# Lipo.net
KiCad netlist of a schematic drawn in EAGLE
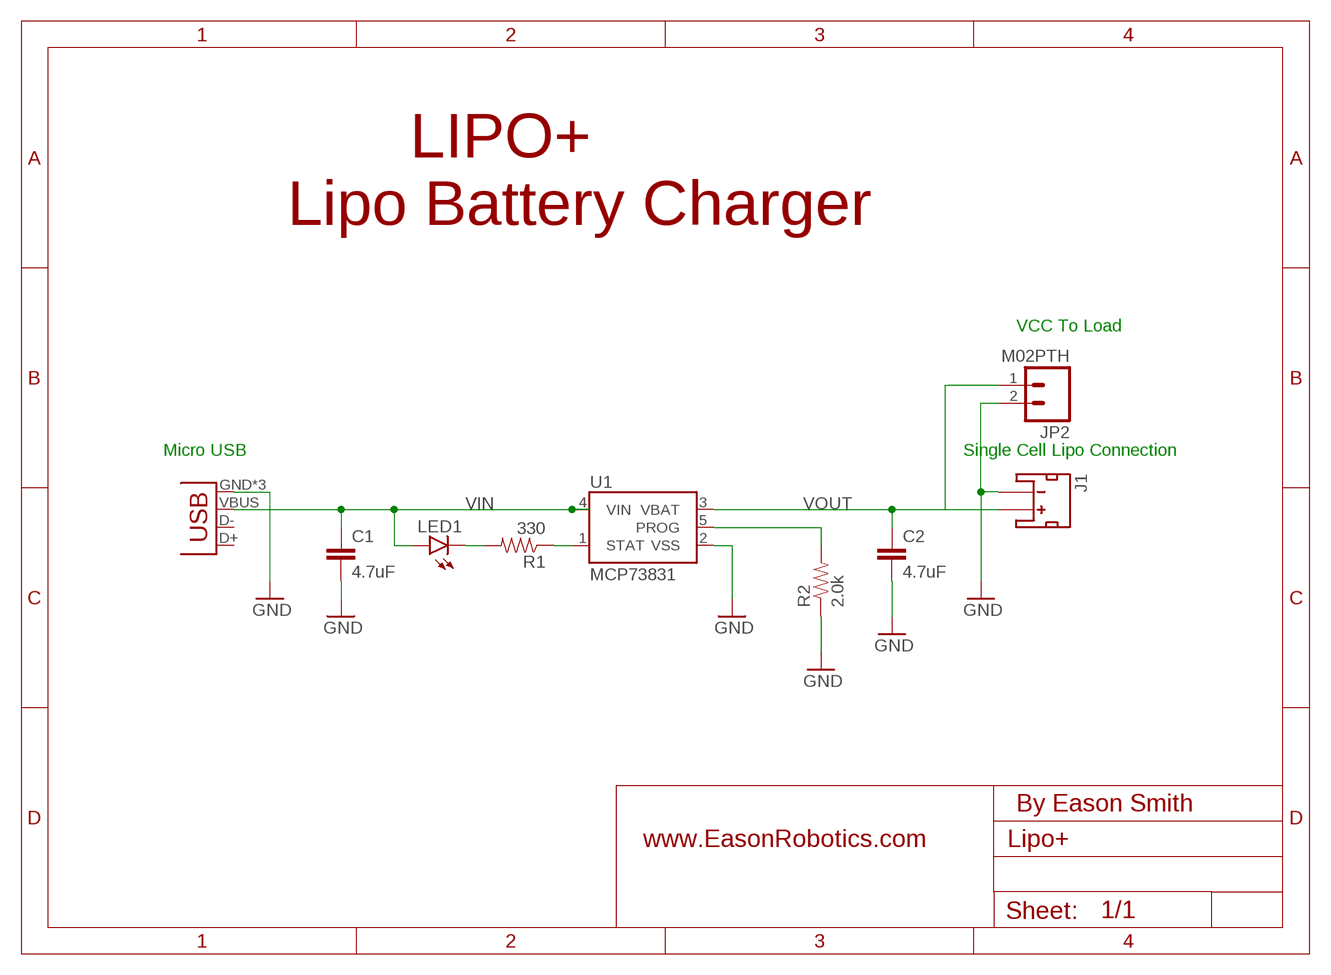
[diagram p0: schematic, sheet 1]

(export (version "E")
  (design (tool "Eeschema 10.0.6"))
  (components
    (comp (ref "C1")
      (value "4.7uF")
      (footprint "eagle-import:0603-CAP")
      (libsource (lib "eagle-import") (part "4.7UF-6.3V-10%(0603)0603"))
    )
    (comp (ref "C2")
      (value "4.7uF")
      (footprint "eagle-import:0603-CAP")
      (libsource (lib "eagle-import") (part "4.7UF-6.3V-10%(0603)0603"))
    )
    (comp (ref "J1")
      (value "JST_2MM_MALE")
      (footprint "eagle-import:JST-2-SMD")
      (libsource (lib "eagle-import") (part "JST_2MM_MALE"))
    )
    (comp (ref "JP1")
      (value "USB-MICROB")
      (footprint "eagle-import:USB-MICROB")
      (libsource (lib "eagle-import") (part "USB-MICROB"))
    )
    (comp (ref "JP2")
      (value "M02PTH")
      (footprint "eagle-import:1X02")
      (libsource (lib "eagle-import") (part "M02PTH"))
    )
    (comp (ref "LED1")
      (value "LED0603")
      (footprint "eagle-import:LED-0603")
      (libsource (lib "eagle-import") (part "LED0603"))
    )
    (comp (ref "R1")
      (value "330")
      (footprint "eagle-import:0603-RES")
      (libsource (lib "eagle-import") (part "330OHM1/10W1%(0603)"))
    )
    (comp (ref "R2")
      (value "2.0k")
      (footprint "eagle-import:0603-RES")
      (libsource (lib "eagle-import") (part "2.0KOHM1/10W5%(0603)"))
    )
    (comp (ref "U1")
      (value "MCP73831")
      (footprint "eagle-import:SOT23-5")
      (libsource (lib "eagle-import") (part "MCP73831"))
    )
  )
  (nets
    (net (code "1") (name "/VIN") (class "Default")
      (node (ref "C1") (pin "1") (pinfunction "1_1") (pintype "passive"))
      (node (ref "JP1") (pin "VBUS") (pinfunction "VBUS_VBUS") (pintype "bidirectional"))
      (node (ref "LED1") (pin "A") (pinfunction "A_A") (pintype "passive"))
      (node (ref "U1") (pin "4") (pinfunction "VIN_4") (pintype "power_in"))
    )
    (net (code "2") (name "/VOUT") (class "Default")
      (node (ref "C2") (pin "1") (pinfunction "1_1") (pintype "passive"))
      (node (ref "J1") (pin "2") (pinfunction "+_2") (pintype "bidirectional"))
      (node (ref "JP2") (pin "1") (pinfunction "1_1") (pintype "passive"))
      (node (ref "U1") (pin "3") (pinfunction "VBAT_3") (pintype "power_in"))
    )
    (net (code "3") (name "GND") (class "Default")
      (node (ref "C1") (pin "2") (pinfunction "2_2") (pintype "passive"))
      (node (ref "C2") (pin "2") (pinfunction "2_2") (pintype "passive"))
      (node (ref "J1") (pin "1") (pinfunction "-_1") (pintype "bidirectional"))
      (node (ref "JP1") (pin "GND") (pinfunction "GND_GND") (pintype "bidirectional"))
      (node (ref "JP1") (pin "MT1") (pinfunction "GND_MT1") (pintype "bidirectional"))
      (node (ref "JP1") (pin "MT2") (pinfunction "GND_MT2") (pintype "bidirectional"))
      (node (ref "JP2") (pin "2") (pinfunction "2_2") (pintype "passive"))
      (node (ref "R2") (pin "1") (pinfunction "1_1") (pintype "passive"))
      (node (ref "U1") (pin "2") (pinfunction "VSS_2") (pintype "power_in"))
    )
    (net (code "4") (name "Net-(LED1-PadC)") (class "Default")
      (node (ref "LED1") (pin "C") (pinfunction "C_C") (pintype "passive"))
      (node (ref "R1") (pin "2") (pinfunction "2_2") (pintype "passive"))
    )
    (net (code "5") (name "Net-(U1-PROG)") (class "Default")
      (node (ref "R2") (pin "2") (pinfunction "2_2") (pintype "passive"))
      (node (ref "U1") (pin "5") (pinfunction "PROG_5") (pintype "input"))
    )
    (net (code "6") (name "Net-(U1-STAT)") (class "Default")
      (node (ref "R1") (pin "1") (pinfunction "1_1") (pintype "passive"))
      (node (ref "U1") (pin "1") (pinfunction "STAT_1") (pintype "output"))
    )
    (net (code "7") (name "unconnected-(J1-PAD1-PadNC1)") (class "Default")
      (node (ref "J1") (pin "NC1") (pinfunction "PAD1_NC1") (pintype "bidirectional"))
    )
    (net (code "8") (name "unconnected-(J1-PAD2-PadNC2)") (class "Default")
      (node (ref "J1") (pin "NC2") (pinfunction "PAD2_NC2") (pintype "bidirectional"))
    )
    (net (code "9") (name "unconnected-(JP1-PadD+)") (class "Default")
      (node (ref "JP1") (pin "D+") (pinfunction "D+_D+") (pintype "bidirectional"))
    )
    (net (code "10") (name "unconnected-(JP1-PadD-)") (class "Default")
      (node (ref "JP1") (pin "D-") (pinfunction "D-_D-") (pintype "bidirectional"))
    )
  )
)
